# MCU_GPIO.net
KiCad netlist of a schematic drawn in Altium Designer
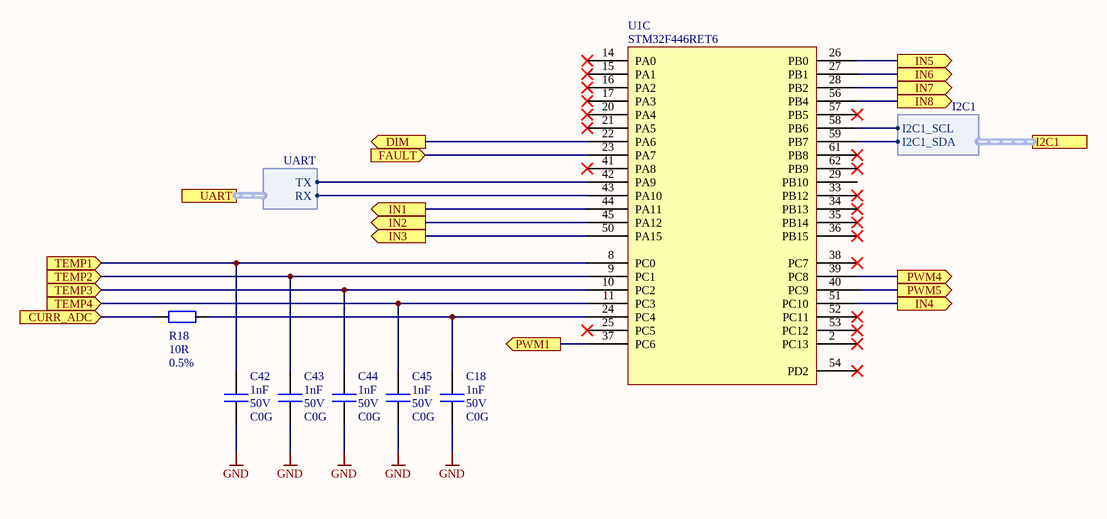
[diagram p0: MCU_GPIO.SchDoc]

(export (version "E")
  (design (tool "Eeschema 10.0.6"))
  (components
    (comp (ref "C18")
      (value "1nF")
      (footprint "C_0603")
      (description "Capacitor")
      (fields
        (field (name "VOLTAGE") "50V")
        (field (name "DIELECTRIC") "C0G")
        (field (name "PART NUMBER") "C_1nF_50V_0603")
        (field (name "MANUFACTURER") "Kemet")
      )
      (libsource (lib "ProgresjaSpace") (part "C"))
    )
    (comp (ref "C42")
      (value "1nF")
      (footprint "C_0603")
      (description "Capacitor")
      (fields
        (field (name "VOLTAGE") "50V")
        (field (name "DIELECTRIC") "C0G")
        (field (name "PART NUMBER") "C_1nF_50V_0603")
        (field (name "MANUFACTURER") "Kemet")
      )
      (libsource (lib "ProgresjaSpace") (part "C"))
    )
    (comp (ref "C43")
      (value "1nF")
      (footprint "C_0603")
      (description "Capacitor")
      (fields
        (field (name "VOLTAGE") "50V")
        (field (name "DIELECTRIC") "C0G")
        (field (name "PART NUMBER") "C_1nF_50V_0603")
        (field (name "MANUFACTURER") "Kemet")
      )
      (libsource (lib "ProgresjaSpace") (part "C"))
    )
    (comp (ref "C44")
      (value "1nF")
      (footprint "C_0603")
      (description "Capacitor")
      (fields
        (field (name "VOLTAGE") "50V")
        (field (name "DIELECTRIC") "C0G")
        (field (name "PART NUMBER") "C_1nF_50V_0603")
        (field (name "MANUFACTURER") "Kemet")
      )
      (libsource (lib "ProgresjaSpace") (part "C"))
    )
    (comp (ref "C45")
      (value "1nF")
      (footprint "C_0603")
      (description "Capacitor")
      (fields
        (field (name "VOLTAGE") "50V")
        (field (name "DIELECTRIC") "C0G")
        (field (name "PART NUMBER") "C_1nF_50V_0603")
        (field (name "MANUFACTURER") "Kemet")
      )
      (libsource (lib "ProgresjaSpace") (part "C"))
    )
    (comp (ref "R18")
      (value "10R")
      (footprint "R_0603")
      (fields
        (field (name "TOLERANCE") "0.5%")
        (field (name "PART NUMBER") "R_10R_75V_0603")
        (field (name "VOLTAGE") "75V")
        (field (name "MANUFACTURER") "Vishay")
      )
      (libsource (lib "ProgresjaSpace") (part "R"))
    )
    (comp (ref "U1")
      (value "STM32F446RET6")
      (footprint "LQFP64")
      (description "ARM Microcontroller, Cortex-M4 core")
      (fields (field (name "MANUFACTURER") "St") (field (name "Comment") "MCU_STM32F446RET6"))
      (libsource (lib "ProgresjaSpace") (part "MCU_STM32F446RET6"))
    )
  )
  (nets
    (net (code "3") (name "/CURR_ADC") (class "Default")
      (node (ref "R18") (pin "1") (pinfunction "1_1") (pintype "passive"))
    )
    (net (code "4") (name "/DIM") (class "Default")
      (node (ref "U1") (pin "22") (pinfunction "PA6_22") (pintype "passive"))
    )
    (net (code "5") (name "/FAULT") (class "Default")
      (node (ref "U1") (pin "23") (pinfunction "PA7_23") (pintype "passive"))
    )
    (net (code "6") (name "/I2C1_SCL") (class "Default")
      (node (ref "U1") (pin "58") (pinfunction "PB6_58") (pintype "passive"))
    )
    (net (code "7") (name "/I2C1_SDA") (class "Default")
      (node (ref "U1") (pin "59") (pinfunction "PB7_59") (pintype "passive"))
    )
    (net (code "8") (name "/IN1") (class "Default")
      (node (ref "U1") (pin "44") (pinfunction "PA11_44") (pintype "passive"))
    )
    (net (code "9") (name "/IN2") (class "Default")
      (node (ref "U1") (pin "45") (pinfunction "PA12_45") (pintype "passive"))
    )
    (net (code "10") (name "/IN3") (class "Default")
      (node (ref "U1") (pin "50") (pinfunction "PA15_50") (pintype "passive"))
    )
    (net (code "11") (name "/IN4") (class "Default")
      (node (ref "U1") (pin "51") (pinfunction "PC10_51") (pintype "passive"))
    )
    (net (code "12") (name "/IN5") (class "Default")
      (node (ref "U1") (pin "26") (pinfunction "PB0_26") (pintype "passive"))
    )
    (net (code "13") (name "/IN6") (class "Default")
      (node (ref "U1") (pin "27") (pinfunction "PB1_27") (pintype "passive"))
    )
    (net (code "14") (name "/IN7") (class "Default")
      (node (ref "U1") (pin "28") (pinfunction "PB2_28") (pintype "passive"))
    )
    (net (code "15") (name "/IN8") (class "Default")
      (node (ref "U1") (pin "56") (pinfunction "PB4_56") (pintype "passive"))
    )
    (net (code "16") (name "/PWM1") (class "Default")
      (node (ref "U1") (pin "37") (pinfunction "PC6_37") (pintype "passive"))
    )
    (net (code "17") (name "/PWM4") (class "Default")
      (node (ref "U1") (pin "39") (pinfunction "PC8_39") (pintype "passive"))
    )
    (net (code "18") (name "/PWM5") (class "Default")
      (node (ref "U1") (pin "40") (pinfunction "PC9_40") (pintype "passive"))
    )
    (net (code "19") (name "/RX") (class "Default")
      (node (ref "U1") (pin "43") (pinfunction "PA10_43") (pintype "passive"))
    )
    (net (code "20") (name "/TEMP1") (class "Default")
      (node (ref "C42") (pin "1") (pinfunction "1_1") (pintype "passive"))
      (node (ref "U1") (pin "8") (pinfunction "PC0_8") (pintype "passive"))
    )
    (net (code "21") (name "/TEMP2") (class "Default")
      (node (ref "C43") (pin "1") (pinfunction "1_1") (pintype "passive"))
      (node (ref "U1") (pin "9") (pinfunction "PC1_9") (pintype "passive"))
    )
    (net (code "22") (name "/TEMP3") (class "Default")
      (node (ref "C44") (pin "1") (pinfunction "1_1") (pintype "passive"))
      (node (ref "U1") (pin "10") (pinfunction "PC2_10") (pintype "passive"))
    )
    (net (code "23") (name "/TEMP4") (class "Default")
      (node (ref "C45") (pin "1") (pinfunction "1_1") (pintype "passive"))
      (node (ref "U1") (pin "11") (pinfunction "PC3_11") (pintype "passive"))
    )
    (net (code "24") (name "/TX") (class "Default")
      (node (ref "U1") (pin "42") (pinfunction "PA9_42") (pintype "passive"))
    )
    (net (code "27") (name "GND") (class "Default")
      (node (ref "C18") (pin "2") (pinfunction "2_2") (pintype "passive"))
      (node (ref "C42") (pin "2") (pinfunction "2_2") (pintype "passive"))
      (node (ref "C43") (pin "2") (pinfunction "2_2") (pintype "passive"))
      (node (ref "C44") (pin "2") (pinfunction "2_2") (pintype "passive"))
      (node (ref "C45") (pin "2") (pinfunction "2_2") (pintype "passive"))
    )
    (net (code "28") (name "Net-(U1C-PC4)") (class "Default")
      (node (ref "C18") (pin "1") (pinfunction "1_1") (pintype "passive"))
      (node (ref "R18") (pin "2") (pinfunction "2_2") (pintype "passive"))
      (node (ref "U1") (pin "24") (pinfunction "PC4_24") (pintype "passive"))
    )
    (net (code "29") (name "unconnected-(U1C-PA0-Pad14)") (class "Default")
      (node (ref "U1") (pin "14") (pinfunction "PA0_14") (pintype "passive+no_connect"))
    )
    (net (code "30") (name "unconnected-(U1C-PA1-Pad15)") (class "Default")
      (node (ref "U1") (pin "15") (pinfunction "PA1_15") (pintype "passive+no_connect"))
    )
    (net (code "31") (name "unconnected-(U1C-PA2-Pad16)") (class "Default")
      (node (ref "U1") (pin "16") (pinfunction "PA2_16") (pintype "passive+no_connect"))
    )
    (net (code "32") (name "unconnected-(U1C-PA3-Pad17)") (class "Default")
      (node (ref "U1") (pin "17") (pinfunction "PA3_17") (pintype "passive+no_connect"))
    )
    (net (code "33") (name "unconnected-(U1C-PA4-Pad20)") (class "Default")
      (node (ref "U1") (pin "20") (pinfunction "PA4_20") (pintype "passive+no_connect"))
    )
    (net (code "34") (name "unconnected-(U1C-PA5-Pad21)") (class "Default")
      (node (ref "U1") (pin "21") (pinfunction "PA5_21") (pintype "passive+no_connect"))
    )
    (net (code "35") (name "unconnected-(U1C-PA8-Pad41)") (class "Default")
      (node (ref "U1") (pin "41") (pinfunction "PA8_41") (pintype "passive+no_connect"))
    )
    (net (code "36") (name "unconnected-(U1C-PB5-Pad57)") (class "Default")
      (node (ref "U1") (pin "57") (pinfunction "PB5_57") (pintype "passive+no_connect"))
    )
    (net (code "37") (name "unconnected-(U1C-PB8-Pad61)") (class "Default")
      (node (ref "U1") (pin "61") (pinfunction "PB8_61") (pintype "passive+no_connect"))
    )
    (net (code "38") (name "unconnected-(U1C-PB9-Pad62)") (class "Default")
      (node (ref "U1") (pin "62") (pinfunction "PB9_62") (pintype "passive+no_connect"))
    )
    (net (code "39") (name "unconnected-(U1C-PB10-Pad29)") (class "Default")
      (node (ref "U1") (pin "29") (pinfunction "PB10_29") (pintype "passive"))
    )
    (net (code "40") (name "unconnected-(U1C-PB12-Pad33)") (class "Default")
      (node (ref "U1") (pin "33") (pinfunction "PB12_33") (pintype "passive+no_connect"))
    )
    (net (code "41") (name "unconnected-(U1C-PB13-Pad34)") (class "Default")
      (node (ref "U1") (pin "34") (pinfunction "PB13_34") (pintype "passive+no_connect"))
    )
    (net (code "42") (name "unconnected-(U1C-PB14-Pad35)") (class "Default")
      (node (ref "U1") (pin "35") (pinfunction "PB14_35") (pintype "passive+no_connect"))
    )
    (net (code "43") (name "unconnected-(U1C-PB15-Pad36)") (class "Default")
      (node (ref "U1") (pin "36") (pinfunction "PB15_36") (pintype "passive+no_connect"))
    )
    (net (code "44") (name "unconnected-(U1C-PC5-Pad25)") (class "Default")
      (node (ref "U1") (pin "25") (pinfunction "PC5_25") (pintype "passive+no_connect"))
    )
    (net (code "45") (name "unconnected-(U1C-PC7-Pad38)") (class "Default")
      (node (ref "U1") (pin "38") (pinfunction "PC7_38") (pintype "passive+no_connect"))
    )
    (net (code "46") (name "unconnected-(U1C-PC11-Pad52)") (class "Default")
      (node (ref "U1") (pin "52") (pinfunction "PC11_52") (pintype "passive+no_connect"))
    )
    (net (code "47") (name "unconnected-(U1C-PC12-Pad53)") (class "Default")
      (node (ref "U1") (pin "53") (pinfunction "PC12_53") (pintype "passive+no_connect"))
    )
    (net (code "48") (name "unconnected-(U1C-PC13-Pad2)") (class "Default")
      (node (ref "U1") (pin "2") (pinfunction "PC13_2") (pintype "passive+no_connect"))
    )
    (net (code "49") (name "unconnected-(U1C-PD2-Pad54)") (class "Default")
      (node (ref "U1") (pin "54") (pinfunction "PD2_54") (pintype "passive+no_connect"))
    )
  )
)
